# AmplifierHardwareSupply.net
KiCad netlist of a schematic drawn in EAGLE
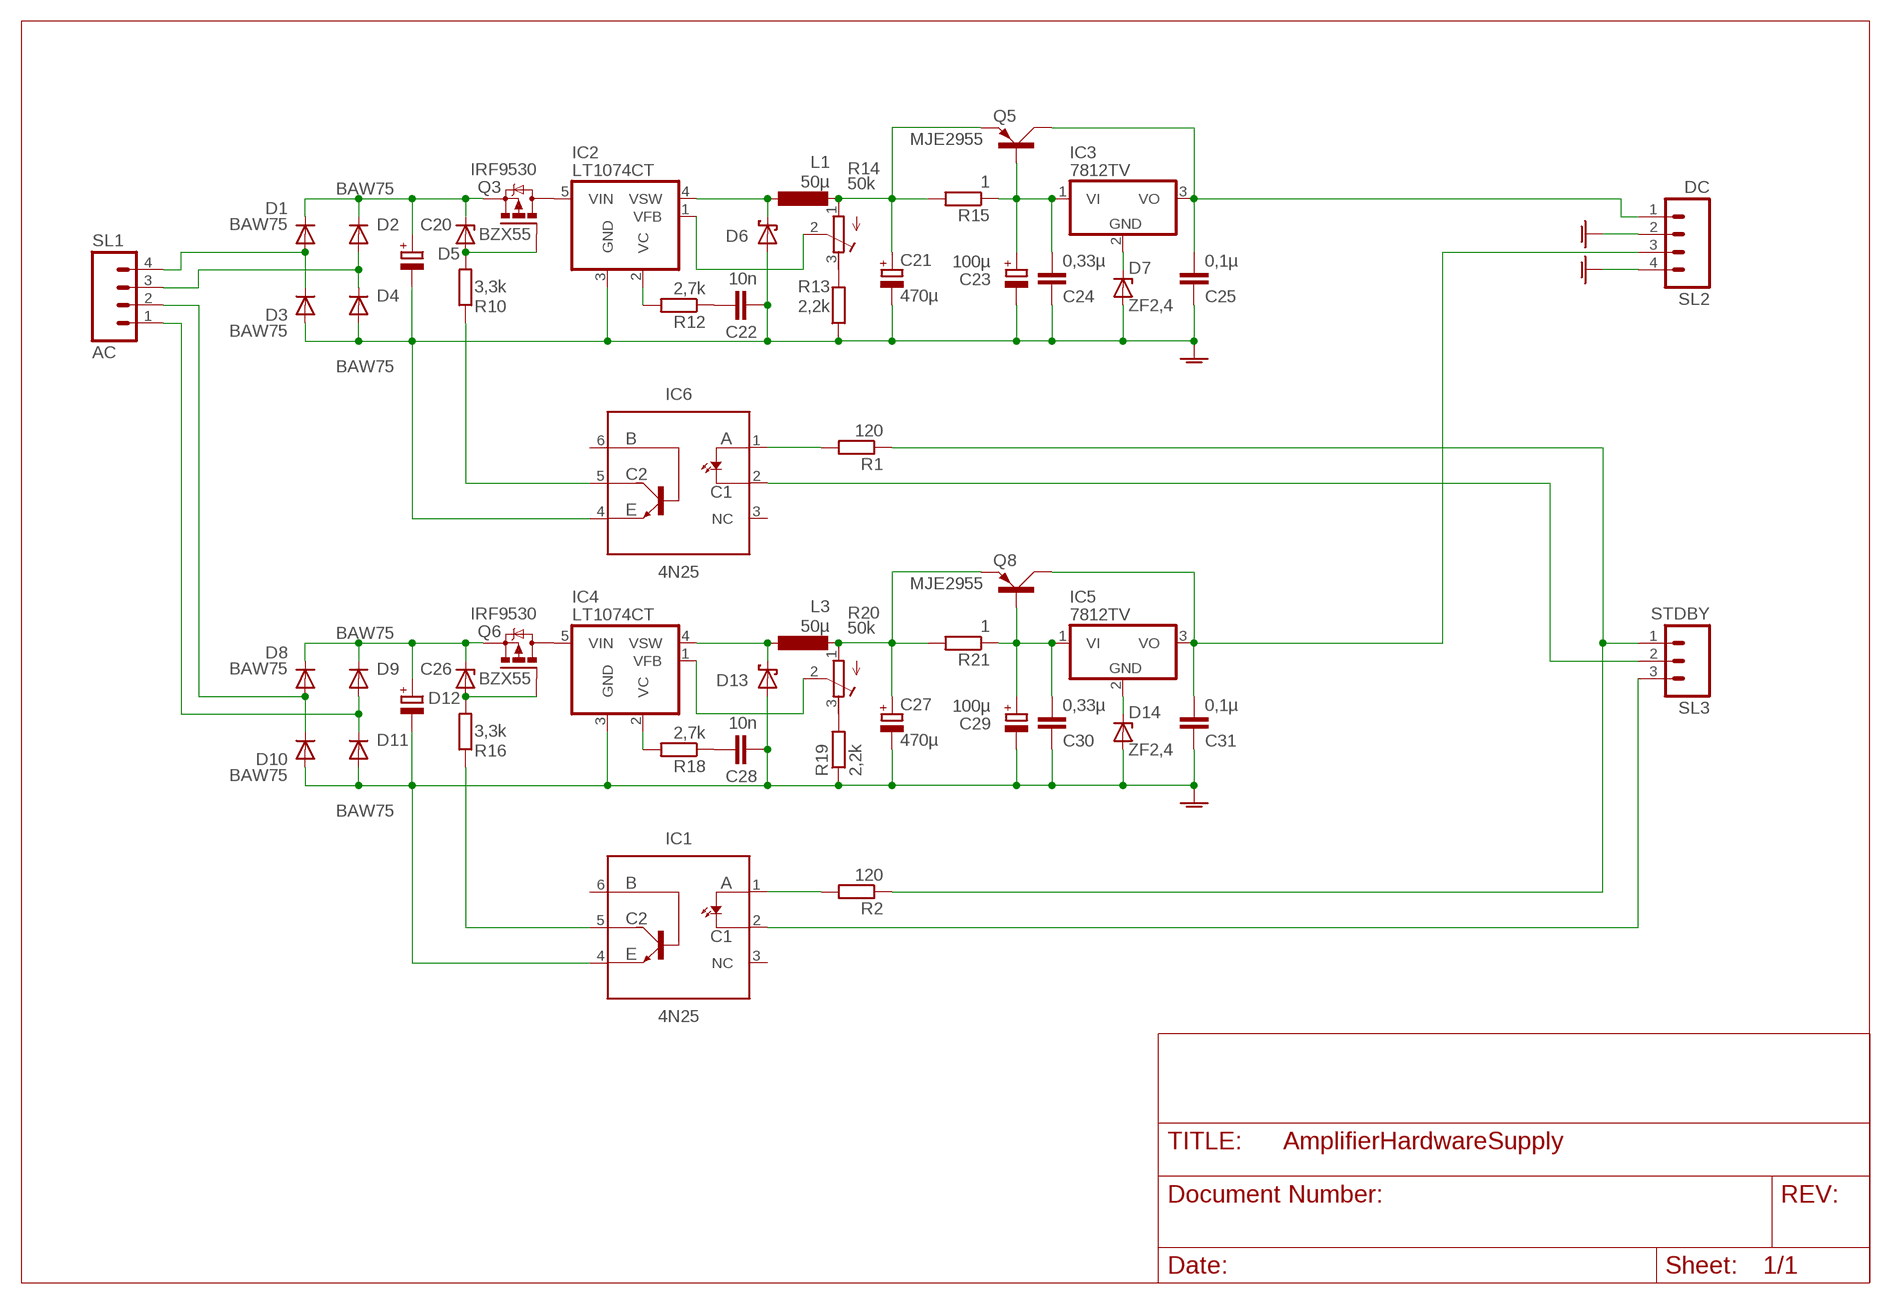
[diagram p0: schematic, sheet 1]

(export (version "E")
  (design (tool "Eeschema 10.0.6"))
  (components
    (comp (ref "C20")
      (value "CPOL-EUE5-10.5")
      (footprint "eagle-import:E5-10,5")
      (libsource (lib "eagle-import") (part "CPOL-EUE5-10.5"))
    )
    (comp (ref "C21")
      (value "470µ")
      (footprint "eagle-import:E5-10,5")
      (libsource (lib "eagle-import") (part "CPOL-EUE5-10.5"))
    )
    (comp (ref "C22")
      (value "10n")
      (footprint "eagle-import:C025-024X044")
      (libsource (lib "eagle-import") (part "C-EU025-024X044"))
    )
    (comp (ref "C23")
      (value "100µ")
      (footprint "eagle-import:E5-10,5")
      (libsource (lib "eagle-import") (part "CPOL-EUE5-10.5"))
    )
    (comp (ref "C24")
      (value "0,33µ")
      (footprint "eagle-import:C025-024X044")
      (libsource (lib "eagle-import") (part "C-EU025-024X044"))
    )
    (comp (ref "C25")
      (value "0,1µ")
      (footprint "eagle-import:C025-024X044")
      (libsource (lib "eagle-import") (part "C-EU025-024X044"))
    )
    (comp (ref "C26")
      (value "CPOL-EUE5-10.5")
      (footprint "eagle-import:E5-10,5")
      (libsource (lib "eagle-import") (part "CPOL-EUE5-10.5"))
    )
    (comp (ref "C27")
      (value "470µ")
      (footprint "eagle-import:E5-10,5")
      (libsource (lib "eagle-import") (part "CPOL-EUE5-10.5"))
    )
    (comp (ref "C28")
      (value "10n")
      (footprint "eagle-import:C025-024X044")
      (libsource (lib "eagle-import") (part "C-EU025-024X044"))
    )
    (comp (ref "C29")
      (value "100µ")
      (footprint "eagle-import:E5-10,5")
      (libsource (lib "eagle-import") (part "CPOL-EUE5-10.5"))
    )
    (comp (ref "C30")
      (value "0,33µ")
      (footprint "eagle-import:C025-024X044")
      (libsource (lib "eagle-import") (part "C-EU025-024X044"))
    )
    (comp (ref "C31")
      (value "0,1µ")
      (footprint "eagle-import:C025-024X044")
      (libsource (lib "eagle-import") (part "C-EU025-024X044"))
    )
    (comp (ref "D1")
      (value "BAW75")
      (footprint "eagle-import:DO35-10")
      (libsource (lib "eagle-import") (part "BAW75"))
    )
    (comp (ref "D2")
      (value "BAW75")
      (footprint "eagle-import:DO35-10")
      (libsource (lib "eagle-import") (part "BAW75"))
    )
    (comp (ref "D3")
      (value "BAW75")
      (footprint "eagle-import:DO35-10")
      (libsource (lib "eagle-import") (part "BAW75"))
    )
    (comp (ref "D4")
      (value "BAW75")
      (footprint "eagle-import:DO35-10")
      (libsource (lib "eagle-import") (part "BAW75"))
    )
    (comp (ref "D5")
      (value "BZX55")
      (footprint "eagle-import:DO35Z10")
      (libsource (lib "eagle-import") (part "BZX55"))
    )
    (comp (ref "D6")
      (value "SCHOTTKY-DIODEDO35-7")
      (footprint "eagle-import:DO35-7")
      (libsource (lib "eagle-import") (part "SCHOTTKY-DIODEDO35-7"))
    )
    (comp (ref "D7")
      (value "ZF2,4")
      (footprint "eagle-import:DO34Z7")
      (libsource (lib "eagle-import") (part "BZV10"))
    )
    (comp (ref "D8")
      (value "BAW75")
      (footprint "eagle-import:DO35-10")
      (libsource (lib "eagle-import") (part "BAW75"))
    )
    (comp (ref "D9")
      (value "BAW75")
      (footprint "eagle-import:DO35-10")
      (libsource (lib "eagle-import") (part "BAW75"))
    )
    (comp (ref "D10")
      (value "BAW75")
      (footprint "eagle-import:DO35-10")
      (libsource (lib "eagle-import") (part "BAW75"))
    )
    (comp (ref "D11")
      (value "BAW75")
      (footprint "eagle-import:DO35-10")
      (libsource (lib "eagle-import") (part "BAW75"))
    )
    (comp (ref "D12")
      (value "BZX55")
      (footprint "eagle-import:DO35Z10")
      (libsource (lib "eagle-import") (part "BZX55"))
    )
    (comp (ref "D13")
      (value "SCHOTTKY-DIODEDO35-7")
      (footprint "eagle-import:DO35-7")
      (libsource (lib "eagle-import") (part "SCHOTTKY-DIODEDO35-7"))
    )
    (comp (ref "D14")
      (value "ZF2,4")
      (footprint "eagle-import:DO34Z7")
      (libsource (lib "eagle-import") (part "BZV10"))
    )
    (comp (ref "IC1")
      (value "4N25")
      (footprint "eagle-import:DIP762W60P254L712H480Q6B")
      (fields (field (name "MANUFACTURER") "Vishay"))
      (libsource (lib "eagle-import") (part "4N25"))
    )
    (comp (ref "IC2")
      (value "LT1074CT")
      (footprint "eagle-import:TO220-5")
      (libsource (lib "eagle-import") (part "LT1074TC"))
    )
    (comp (ref "IC3")
      (value "7812TV")
      (footprint "eagle-import:TO220V")
      (libsource (lib "eagle-import") (part "78TV12"))
    )
    (comp (ref "IC4")
      (value "LT1074CT")
      (footprint "eagle-import:TO220-5")
      (libsource (lib "eagle-import") (part "LT1074TC"))
    )
    (comp (ref "IC5")
      (value "7812TV")
      (footprint "eagle-import:TO220V")
      (libsource (lib "eagle-import") (part "78TV12"))
    )
    (comp (ref "IC6")
      (value "4N25")
      (footprint "eagle-import:DIP762W60P254L712H480Q6B")
      (fields (field (name "MANUFACTURER") "Vishay"))
      (libsource (lib "eagle-import") (part "4N25"))
    )
    (comp (ref "L1")
      (value "50µ")
      (footprint "eagle-import:TJ3-U1")
      (libsource (lib "eagle-import") (part "L-EUTJ3-U1"))
    )
    (comp (ref "L3")
      (value "50µ")
      (footprint "eagle-import:TJ3-U1")
      (libsource (lib "eagle-import") (part "L-EUTJ3-U1"))
    )
    (comp (ref "Q3")
      (value "IRF9530")
      (footprint "eagle-import:TO220BV")
      (libsource (lib "eagle-import") (part "IRF9530"))
    )
    (comp (ref "Q5")
      (value "MJE2955")
      (footprint "eagle-import:TO220AV")
      (libsource (lib "eagle-import") (part "MJE2955"))
    )
    (comp (ref "Q6")
      (value "IRF9530")
      (footprint "eagle-import:TO220BV")
      (libsource (lib "eagle-import") (part "IRF9530"))
    )
    (comp (ref "Q8")
      (value "MJE2955")
      (footprint "eagle-import:TO220AV")
      (libsource (lib "eagle-import") (part "MJE2955"))
    )
    (comp (ref "R1")
      (value "120")
      (footprint "eagle-import:0207_2V")
      (libsource (lib "eagle-import") (part "R-EU_0207/2V"))
    )
    (comp (ref "R2")
      (value "120")
      (footprint "eagle-import:0207_2V")
      (libsource (lib "eagle-import") (part "R-EU_0207/2V"))
    )
    (comp (ref "R10")
      (value "3,3k")
      (footprint "eagle-import:0207_2V")
      (libsource (lib "eagle-import") (part "R-EU_0207/2V"))
    )
    (comp (ref "R12")
      (value "2,7k")
      (footprint "eagle-import:0207_2V")
      (libsource (lib "eagle-import") (part "R-EU_0207/2V"))
    )
    (comp (ref "R13")
      (value "2,2k")
      (footprint "eagle-import:0207_2V")
      (libsource (lib "eagle-import") (part "R-EU_0207/2V"))
    )
    (comp (ref "R14")
      (value "50k")
      (footprint "eagle-import:RTRIM64W")
      (libsource (lib "eagle-import") (part "R-TRIMM64W"))
    )
    (comp (ref "R15")
      (value "1")
      (footprint "eagle-import:0207_2V")
      (libsource (lib "eagle-import") (part "R-EU_0207/2V"))
    )
    (comp (ref "R16")
      (value "3,3k")
      (footprint "eagle-import:0207_2V")
      (libsource (lib "eagle-import") (part "R-EU_0207/2V"))
    )
    (comp (ref "R18")
      (value "2,7k")
      (footprint "eagle-import:0207_2V")
      (libsource (lib "eagle-import") (part "R-EU_0207/2V"))
    )
    (comp (ref "R19")
      (value "2,2k")
      (footprint "eagle-import:0207_2V")
      (libsource (lib "eagle-import") (part "R-EU_0207/2V"))
    )
    (comp (ref "R20")
      (value "50k")
      (footprint "eagle-import:RTRIM64W")
      (libsource (lib "eagle-import") (part "R-TRIMM64W"))
    )
    (comp (ref "R21")
      (value "1")
      (footprint "eagle-import:0207_2V")
      (libsource (lib "eagle-import") (part "R-EU_0207/2V"))
    )
    (comp (ref "SL1")
      (value "AC")
      (footprint "eagle-import:04P")
      (libsource (lib "eagle-import") (part "M04"))
    )
    (comp (ref "SL2")
      (value "DC")
      (footprint "eagle-import:04P")
      (libsource (lib "eagle-import") (part "M04"))
    )
    (comp (ref "SL3")
      (value "STDBY")
      (footprint "eagle-import:03P")
      (libsource (lib "eagle-import") (part "M03"))
    )
  )
  (nets
    (net (code "1") (name "AGND") (class "Default")
      (node (ref "C20") (pin "-") (pinfunction "-_-") (pintype "passive"))
      (node (ref "C21") (pin "-") (pinfunction "-_-") (pintype "passive"))
      (node (ref "C22") (pin "2") (pinfunction "2_2") (pintype "passive"))
      (node (ref "C23") (pin "-") (pinfunction "-_-") (pintype "passive"))
      (node (ref "C24") (pin "1") (pinfunction "1_1") (pintype "passive"))
      (node (ref "C25") (pin "1") (pinfunction "1_1") (pintype "passive"))
      (node (ref "C26") (pin "-") (pinfunction "-_-") (pintype "passive"))
      (node (ref "C27") (pin "-") (pinfunction "-_-") (pintype "passive"))
      (node (ref "C28") (pin "2") (pinfunction "2_2") (pintype "passive"))
      (node (ref "C29") (pin "-") (pinfunction "-_-") (pintype "passive"))
      (node (ref "C30") (pin "1") (pinfunction "1_1") (pintype "passive"))
      (node (ref "C31") (pin "1") (pinfunction "1_1") (pintype "passive"))
      (node (ref "D10") (pin "A") (pinfunction "A_A") (pintype "passive"))
      (node (ref "D11") (pin "A") (pinfunction "A_A") (pintype "passive"))
      (node (ref "D13") (pin "A") (pinfunction "A_A") (pintype "passive"))
      (node (ref "D14") (pin "A") (pinfunction "A_A") (pintype "passive"))
      (node (ref "D3") (pin "A") (pinfunction "A_A") (pintype "passive"))
      (node (ref "D4") (pin "A") (pinfunction "A_A") (pintype "passive"))
      (node (ref "D6") (pin "A") (pinfunction "A_A") (pintype "passive"))
      (node (ref "D7") (pin "A") (pinfunction "A_A") (pintype "passive"))
      (node (ref "IC1") (pin "4") (pinfunction "E_4") (pintype "passive"))
      (node (ref "IC2") (pin "3") (pinfunction "GND_3") (pintype "power_in"))
      (node (ref "IC4") (pin "3") (pinfunction "GND_3") (pintype "power_in"))
      (node (ref "IC6") (pin "4") (pinfunction "E_4") (pintype "passive"))
      (node (ref "R13") (pin "1") (pinfunction "1_1") (pintype "passive"))
      (node (ref "R19") (pin "1") (pinfunction "1_1") (pintype "passive"))
      (node (ref "SL2") (pin "2") (pinfunction "2_2") (pintype "passive"))
      (node (ref "SL2") (pin "4") (pinfunction "4_4") (pintype "passive"))
    )
    (net (code "2") (name "Net-(C20-Pad+)") (class "Default")
      (node (ref "C20") (pin "+") (pinfunction "+_+") (pintype "passive"))
      (node (ref "D1") (pin "C") (pinfunction "C_C") (pintype "passive"))
      (node (ref "D2") (pin "C") (pinfunction "C_C") (pintype "passive"))
      (node (ref "D5") (pin "C") (pinfunction "C_C") (pintype "passive"))
      (node (ref "Q3") (pin "S") (pinfunction "S_S") (pintype "passive"))
    )
    (net (code "3") (name "Net-(C22-Pad1)") (class "Default")
      (node (ref "C22") (pin "1") (pinfunction "1_1") (pintype "passive"))
      (node (ref "R12") (pin "1") (pinfunction "1_1") (pintype "passive"))
    )
    (net (code "4") (name "Net-(C26-Pad+)") (class "Default")
      (node (ref "C26") (pin "+") (pinfunction "+_+") (pintype "passive"))
      (node (ref "D12") (pin "C") (pinfunction "C_C") (pintype "passive"))
      (node (ref "D8") (pin "C") (pinfunction "C_C") (pintype "passive"))
      (node (ref "D9") (pin "C") (pinfunction "C_C") (pintype "passive"))
      (node (ref "Q6") (pin "S") (pinfunction "S_S") (pintype "passive"))
    )
    (net (code "5") (name "Net-(C28-Pad1)") (class "Default")
      (node (ref "C28") (pin "1") (pinfunction "1_1") (pintype "passive"))
      (node (ref "R18") (pin "1") (pinfunction "1_1") (pintype "passive"))
    )
    (net (code "6") (name "Net-(D1-PadA)") (class "Default")
      (node (ref "D1") (pin "A") (pinfunction "A_A") (pintype "passive"))
      (node (ref "D3") (pin "C") (pinfunction "C_C") (pintype "passive"))
      (node (ref "SL1") (pin "4") (pinfunction "4_4") (pintype "passive"))
    )
    (net (code "7") (name "Net-(D2-PadA)") (class "Default")
      (node (ref "D2") (pin "A") (pinfunction "A_A") (pintype "passive"))
      (node (ref "D4") (pin "C") (pinfunction "C_C") (pintype "passive"))
      (node (ref "SL1") (pin "3") (pinfunction "3_3") (pintype "passive"))
    )
    (net (code "8") (name "Net-(D5-PadA)") (class "Default")
      (node (ref "D5") (pin "A") (pinfunction "A_A") (pintype "passive"))
      (node (ref "Q3") (pin "G") (pinfunction "G_G") (pintype "passive"))
      (node (ref "R10") (pin "2") (pinfunction "2_2") (pintype "passive"))
    )
    (net (code "9") (name "Net-(D10-PadC)") (class "Default")
      (node (ref "D10") (pin "C") (pinfunction "C_C") (pintype "passive"))
      (node (ref "D8") (pin "A") (pinfunction "A_A") (pintype "passive"))
      (node (ref "SL1") (pin "2") (pinfunction "2_2") (pintype "passive"))
    )
    (net (code "10") (name "Net-(D11-PadC)") (class "Default")
      (node (ref "D11") (pin "C") (pinfunction "C_C") (pintype "passive"))
      (node (ref "D9") (pin "A") (pinfunction "A_A") (pintype "passive"))
      (node (ref "SL1") (pin "1") (pinfunction "1_1") (pintype "passive"))
    )
    (net (code "11") (name "Net-(D12-PadA)") (class "Default")
      (node (ref "D12") (pin "A") (pinfunction "A_A") (pintype "passive"))
      (node (ref "Q6") (pin "G") (pinfunction "G_G") (pintype "passive"))
      (node (ref "R16") (pin "2") (pinfunction "2_2") (pintype "passive"))
    )
    (net (code "12") (name "Net-(IC1-A)") (class "Default")
      (node (ref "IC1") (pin "1") (pinfunction "A_1") (pintype "passive"))
      (node (ref "R2") (pin "2") (pinfunction "2_2") (pintype "passive"))
    )
    (net (code "13") (name "Net-(IC1-C1)") (class "Default")
      (node (ref "IC1") (pin "2") (pinfunction "C1_2") (pintype "passive"))
      (node (ref "SL3") (pin "3") (pinfunction "3_3") (pintype "passive"))
    )
    (net (code "14") (name "Net-(IC1-C2)") (class "Default")
      (node (ref "IC1") (pin "5") (pinfunction "C2_5") (pintype "passive"))
      (node (ref "R16") (pin "1") (pinfunction "1_1") (pintype "passive"))
    )
    (net (code "15") (name "Net-(IC2-VC)") (class "Default")
      (node (ref "IC2") (pin "2") (pinfunction "VC_2") (pintype "passive"))
      (node (ref "R12") (pin "2") (pinfunction "2_2") (pintype "passive"))
    )
    (net (code "16") (name "Net-(IC2-VFB)") (class "Default")
      (node (ref "IC2") (pin "1") (pinfunction "VFB_1") (pintype "passive"))
      (node (ref "R14") (pin "2") (pinfunction "S_2") (pintype "passive"))
    )
    (net (code "17") (name "Net-(IC2-VIN)") (class "Default")
      (node (ref "IC2") (pin "5") (pinfunction "VIN_5") (pintype "passive"))
      (node (ref "Q3") (pin "D") (pinfunction "D_D") (pintype "passive"))
    )
    (net (code "18") (name "Net-(IC2-VSW)") (class "Default")
      (node (ref "D6") (pin "C") (pinfunction "C_C") (pintype "passive"))
      (node (ref "IC2") (pin "4") (pinfunction "VSW_4") (pintype "passive"))
      (node (ref "L1") (pin "1") (pinfunction "1_1") (pintype "passive"))
    )
    (net (code "19") (name "Net-(IC3-GND)") (class "Default")
      (node (ref "D7") (pin "C") (pinfunction "C_C") (pintype "passive"))
      (node (ref "IC3") (pin "2") (pinfunction "GND_2") (pintype "passive"))
    )
    (net (code "20") (name "Net-(IC3-VI)") (class "Default")
      (node (ref "C23") (pin "+") (pinfunction "+_+") (pintype "passive"))
      (node (ref "C24") (pin "2") (pinfunction "2_2") (pintype "passive"))
      (node (ref "IC3") (pin "1") (pinfunction "VI_1") (pintype "input"))
      (node (ref "Q5") (pin "B") (pinfunction "B_B") (pintype "passive"))
      (node (ref "R15") (pin "1") (pinfunction "1_1") (pintype "passive"))
    )
    (net (code "21") (name "Net-(IC3-VO)") (class "Default")
      (node (ref "C25") (pin "2") (pinfunction "2_2") (pintype "passive"))
      (node (ref "IC3") (pin "3") (pinfunction "VO_3") (pintype "passive"))
      (node (ref "Q5") (pin "C") (pinfunction "C_C") (pintype "passive"))
      (node (ref "SL2") (pin "1") (pinfunction "1_1") (pintype "passive"))
    )
    (net (code "22") (name "Net-(IC4-VC)") (class "Default")
      (node (ref "IC4") (pin "2") (pinfunction "VC_2") (pintype "passive"))
      (node (ref "R18") (pin "2") (pinfunction "2_2") (pintype "passive"))
    )
    (net (code "23") (name "Net-(IC4-VFB)") (class "Default")
      (node (ref "IC4") (pin "1") (pinfunction "VFB_1") (pintype "passive"))
      (node (ref "R20") (pin "2") (pinfunction "S_2") (pintype "passive"))
    )
    (net (code "24") (name "Net-(IC4-VIN)") (class "Default")
      (node (ref "IC4") (pin "5") (pinfunction "VIN_5") (pintype "passive"))
      (node (ref "Q6") (pin "D") (pinfunction "D_D") (pintype "passive"))
    )
    (net (code "25") (name "Net-(IC4-VSW)") (class "Default")
      (node (ref "D13") (pin "C") (pinfunction "C_C") (pintype "passive"))
      (node (ref "IC4") (pin "4") (pinfunction "VSW_4") (pintype "passive"))
      (node (ref "L3") (pin "1") (pinfunction "1_1") (pintype "passive"))
    )
    (net (code "26") (name "Net-(IC5-GND)") (class "Default")
      (node (ref "D14") (pin "C") (pinfunction "C_C") (pintype "passive"))
      (node (ref "IC5") (pin "2") (pinfunction "GND_2") (pintype "passive"))
    )
    (net (code "27") (name "Net-(IC5-VI)") (class "Default")
      (node (ref "C29") (pin "+") (pinfunction "+_+") (pintype "passive"))
      (node (ref "C30") (pin "2") (pinfunction "2_2") (pintype "passive"))
      (node (ref "IC5") (pin "1") (pinfunction "VI_1") (pintype "input"))
      (node (ref "Q8") (pin "B") (pinfunction "B_B") (pintype "passive"))
      (node (ref "R21") (pin "1") (pinfunction "1_1") (pintype "passive"))
    )
    (net (code "28") (name "Net-(IC5-VO)") (class "Default")
      (node (ref "C31") (pin "2") (pinfunction "2_2") (pintype "passive"))
      (node (ref "IC5") (pin "3") (pinfunction "VO_3") (pintype "passive"))
      (node (ref "Q8") (pin "C") (pinfunction "C_C") (pintype "passive"))
      (node (ref "SL2") (pin "3") (pinfunction "3_3") (pintype "passive"))
    )
    (net (code "29") (name "Net-(IC6-A)") (class "Default")
      (node (ref "IC6") (pin "1") (pinfunction "A_1") (pintype "passive"))
      (node (ref "R1") (pin "2") (pinfunction "2_2") (pintype "passive"))
    )
    (net (code "30") (name "Net-(IC6-C1)") (class "Default")
      (node (ref "IC6") (pin "2") (pinfunction "C1_2") (pintype "passive"))
      (node (ref "SL3") (pin "2") (pinfunction "2_2") (pintype "passive"))
    )
    (net (code "31") (name "Net-(IC6-C2)") (class "Default")
      (node (ref "IC6") (pin "5") (pinfunction "C2_5") (pintype "passive"))
      (node (ref "R10") (pin "1") (pinfunction "1_1") (pintype "passive"))
    )
    (net (code "32") (name "Net-(R1-Pad1)") (class "Default")
      (node (ref "R1") (pin "1") (pinfunction "1_1") (pintype "passive"))
      (node (ref "R2") (pin "1") (pinfunction "1_1") (pintype "passive"))
      (node (ref "SL3") (pin "1") (pinfunction "1_1") (pintype "passive"))
    )
    (net (code "33") (name "Net-(R14-A)") (class "Default")
      (node (ref "R13") (pin "2") (pinfunction "2_2") (pintype "passive"))
      (node (ref "R14") (pin "3") (pinfunction "A_3") (pintype "passive"))
    )
    (net (code "34") (name "Net-(R14-E)") (class "Default")
      (node (ref "C21") (pin "+") (pinfunction "+_+") (pintype "passive"))
      (node (ref "L1") (pin "2") (pinfunction "2_2") (pintype "passive"))
      (node (ref "Q5") (pin "E") (pinfunction "E_E") (pintype "passive"))
      (node (ref "R14") (pin "1") (pinfunction "E_1") (pintype "passive"))
      (node (ref "R15") (pin "2") (pinfunction "2_2") (pintype "passive"))
    )
    (net (code "35") (name "Net-(R20-A)") (class "Default")
      (node (ref "R19") (pin "2") (pinfunction "2_2") (pintype "passive"))
      (node (ref "R20") (pin "3") (pinfunction "A_3") (pintype "passive"))
    )
    (net (code "36") (name "Net-(R20-E)") (class "Default")
      (node (ref "C27") (pin "+") (pinfunction "+_+") (pintype "passive"))
      (node (ref "L3") (pin "2") (pinfunction "2_2") (pintype "passive"))
      (node (ref "Q8") (pin "E") (pinfunction "E_E") (pintype "passive"))
      (node (ref "R20") (pin "1") (pinfunction "E_1") (pintype "passive"))
      (node (ref "R21") (pin "2") (pinfunction "2_2") (pintype "passive"))
    )
    (net (code "37") (name "unconnected-(IC1-B-Pad6)") (class "Default")
      (node (ref "IC1") (pin "6") (pinfunction "B_6") (pintype "passive"))
    )
    (net (code "38") (name "unconnected-(IC1-NC-Pad3)") (class "Default")
      (node (ref "IC1") (pin "3") (pinfunction "NC_3") (pintype "no_connect"))
    )
    (net (code "39") (name "unconnected-(IC6-B-Pad6)") (class "Default")
      (node (ref "IC6") (pin "6") (pinfunction "B_6") (pintype "passive"))
    )
    (net (code "40") (name "unconnected-(IC6-NC-Pad3)") (class "Default")
      (node (ref "IC6") (pin "3") (pinfunction "NC_3") (pintype "no_connect"))
    )
  )
)
